# OpenRing_RGB.net
KiCad netlist of a schematic drawn in Altium Designer
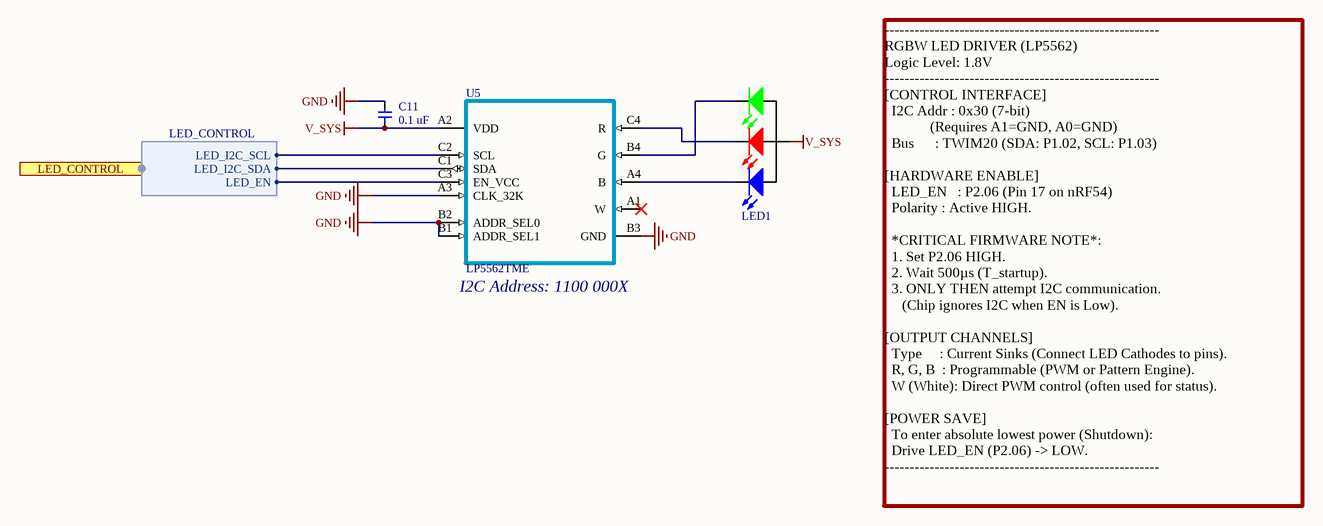
[diagram p0: OpenRing_RGB.SchDoc]

(export (version "E")
  (design (tool "Eeschema 10.0.6"))
  (components
    (comp (ref "C11")
      (value "0.1 uF")
      (footprint "CAPC1005X05N")
      (description "CAP CER 0.1UF 16V X5R 0402")
      (fields
        (field (name "MANUFACTURER") "Murata Electronics")
        (field (name "MANUFACTURER PART NUMBER") "GRM155R61C104KA88D")
      )
      (libsource (lib "OpenRingComponents") (part "GRM155R61C104KA88D"))
    )
    (comp (ref "LED1")
      (value "SML-LX0404SIUPGUSB")
      (footprint "SML-LX0404SIUPGUSB")
      (description "LED Low-Power Tri-Color Blue/Green/Red 465nm/518nm/632nm 2.7V/2.75V/1.95V 4-Pin SMD T/R")
      (fields (field (name "MANUFACTURER") "Lumex"))
      (libsource (lib "OpenRingComponents") (part "SML-LX0404SIUPGUSB"))
    )
    (comp (ref "U5")
      (value "LP5562TME")
      (footprint "BGA12C40P4X3_162X122X68")
      (description "IC LED DRIVER LINEAR DIM 25.5MA")
      (fields
        (field (name "MANUFACTURER") "Texas Instruments")
        (field (name "MANUFACTURER PART NUMBER") "LP5562TME/NOPB")
      )
      (libsource (lib "OpenRingComponents") (part "LP5562TME/NOPB"))
    )
  )
  (nets
    (net (code "2") (name "/LED_EN") (class "Default")
      (node (ref "U5") (pin "C3") (pinfunction "EN_VCC_C3") (pintype "input"))
    )
    (net (code "3") (name "/LED_I2C_SCL") (class "Default")
      (node (ref "U5") (pin "C2") (pinfunction "SCL_C2") (pintype "input"))
    )
    (net (code "4") (name "/LED_I2C_SDA") (class "Default")
      (node (ref "U5") (pin "C1") (pinfunction "SDA_C1") (pintype "bidirectional"))
    )
    (net (code "6") (name "GND") (class "Default")
      (node (ref "C11") (pin "2") (pinfunction "2_2") (pintype "passive"))
      (node (ref "U5") (pin "A3") (pinfunction "CLK_32K_A3") (pintype "input"))
      (node (ref "U5") (pin "B1") (pinfunction "ADDR_SEL1_B1") (pintype "input"))
      (node (ref "U5") (pin "B2") (pinfunction "ADDR_SEL0_B2") (pintype "input"))
      (node (ref "U5") (pin "B3") (pinfunction "GND_B3") (pintype "power_in"))
    )
    (net (code "7") (name "Net-(U5-B)") (class "Default")
      (node (ref "LED1") (pin "3") (pinfunction "K_3") (pintype "passive"))
      (node (ref "U5") (pin "A4") (pinfunction "B_A4") (pintype "input"))
    )
    (net (code "8") (name "Net-(U5-G)") (class "Default")
      (node (ref "LED1") (pin "4") (pinfunction "K_4") (pintype "passive"))
      (node (ref "U5") (pin "B4") (pinfunction "G_B4") (pintype "input"))
    )
    (net (code "9") (name "Net-(U5-R)") (class "Default")
      (node (ref "LED1") (pin "2") (pinfunction "K_2") (pintype "passive"))
      (node (ref "U5") (pin "C4") (pinfunction "R_C4") (pintype "input"))
    )
    (net (code "10") (name "V_SYS") (class "Default")
      (node (ref "C11") (pin "1") (pinfunction "1_1") (pintype "passive"))
      (node (ref "LED1") (pin "1") (pinfunction "A_1") (pintype "passive"))
      (node (ref "U5") (pin "A2") (pinfunction "VDD_A2") (pintype "power_in"))
    )
    (net (code "11") (name "unconnected-(U5-W-PadA1)") (class "Default")
      (node (ref "U5") (pin "A1") (pinfunction "W_A1") (pintype "input+no_connect"))
    )
  )
)
